# ajile_ximea_trigger_adapter.net
KiCad netlist of a schematic drawn in EAGLE
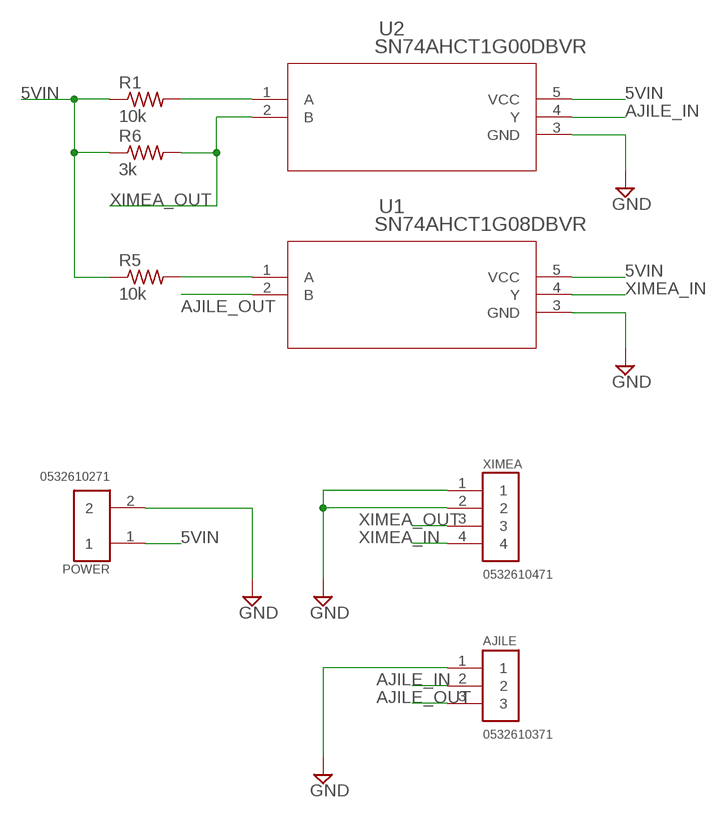
[diagram p0: schematic, sheet 1]

(export (version "E")
  (design (tool "Eeschema 10.0.6"))
  (components
    (comp (ref "AJILE")
      (value "0532610371")
      (footprint "eagle-import:MOLEX_0532610371")
      (fields (field (name "DIGI-KEY_PART_NUMBER") "WM7621CT-ND") (field (name "MF") "Molex, LLC"))
      (libsource (lib "eagle-import") (part "0532610371"))
    )
    (comp (ref "POWER")
      (value "0532610271")
      (footprint "eagle-import:MOLEX_0532610271")
      (fields (field (name "DIGI-KEY_PART_NUMBER") "WM7620CT-ND") (field (name "MF") "Molex, LLC"))
      (libsource (lib "eagle-import") (part "0532610271"))
    )
    (comp (ref "R1")
      (value "10k")
      (footprint "eagle-import:R0603")
      (libsource (lib "eagle-import") (part "R-US_R0603"))
    )
    (comp (ref "R5")
      (value "10k")
      (footprint "eagle-import:R0603")
      (libsource (lib "eagle-import") (part "R-US_R0603"))
    )
    (comp (ref "R6")
      (value "3k")
      (footprint "eagle-import:R0603")
      (libsource (lib "eagle-import") (part "R-US_R0603"))
    )
    (comp (ref "U1")
      (value "SN74AHCT1G08DBVR")
      (footprint "eagle-import:DBV5")
      (libsource (lib "eagle-import") (part "SN74AHCT1G08DBVR"))
    )
    (comp (ref "U2")
      (value "SN74AHCT1G00DBVR")
      (footprint "eagle-import:DBV5")
      (libsource (lib "eagle-import") (part "SN74AHCT1G00DBVR"))
    )
    (comp (ref "XIMEA")
      (value "0532610471")
      (footprint "eagle-import:MOLEX_0532610471")
      (fields (field (name "DIGI-KEY_PART_NUMBER") "WM7622CT-ND") (field (name "MF") "Molex, LLC"))
      (libsource (lib "eagle-import") (part "0532610471"))
    )
  )
  (nets
    (net (code "1") (name "/5VIN") (class "Default")
      (node (ref "POWER") (pin "1") (pinfunction "1_1") (pintype "passive"))
      (node (ref "R1") (pin "1") (pinfunction "1_1") (pintype "passive"))
      (node (ref "R5") (pin "1") (pinfunction "1_1") (pintype "passive"))
      (node (ref "R6") (pin "1") (pinfunction "1_1") (pintype "passive"))
      (node (ref "U1") (pin "5") (pinfunction "VCC_5") (pintype "power_in"))
      (node (ref "U2") (pin "5") (pinfunction "VCC_5") (pintype "power_in"))
    )
    (net (code "2") (name "/AJILE_IN") (class "Default")
      (node (ref "AJILE") (pin "2") (pinfunction "2_2") (pintype "passive"))
      (node (ref "U2") (pin "4") (pinfunction "Y_4") (pintype "output"))
    )
    (net (code "3") (name "/AJILE_OUT") (class "Default")
      (node (ref "AJILE") (pin "3") (pinfunction "3_3") (pintype "passive"))
      (node (ref "U1") (pin "2") (pinfunction "B_2") (pintype "input"))
    )
    (net (code "4") (name "/XIMEA_IN") (class "Default")
      (node (ref "U1") (pin "4") (pinfunction "Y_4") (pintype "output"))
      (node (ref "XIMEA") (pin "4") (pinfunction "4_4") (pintype "passive"))
    )
    (net (code "5") (name "/XIMEA_OUT") (class "Default")
      (node (ref "R6") (pin "2") (pinfunction "2_2") (pintype "passive"))
      (node (ref "U2") (pin "2") (pinfunction "B_2") (pintype "input"))
      (node (ref "XIMEA") (pin "3") (pinfunction "3_3") (pintype "passive"))
    )
    (net (code "6") (name "GND") (class "Default")
      (node (ref "AJILE") (pin "1") (pinfunction "1_1") (pintype "passive"))
      (node (ref "POWER") (pin "2") (pinfunction "2_2") (pintype "passive"))
      (node (ref "U1") (pin "3") (pinfunction "GND_3") (pintype "power_in"))
      (node (ref "U2") (pin "3") (pinfunction "GND_3") (pintype "power_in"))
      (node (ref "XIMEA") (pin "1") (pinfunction "1_1") (pintype "passive"))
      (node (ref "XIMEA") (pin "2") (pinfunction "2_2") (pintype "passive"))
    )
    (net (code "7") (name "Net-(U1-A)") (class "Default")
      (node (ref "R5") (pin "2") (pinfunction "2_2") (pintype "passive"))
      (node (ref "U1") (pin "1") (pinfunction "A_1") (pintype "input"))
    )
    (net (code "8") (name "Net-(U2-A)") (class "Default")
      (node (ref "R1") (pin "2") (pinfunction "2_2") (pintype "passive"))
      (node (ref "U2") (pin "1") (pinfunction "A_1") (pintype "input"))
    )
  )
)
